# Arriquitaun.net
KiCad netlist of a schematic drawn in Altium Designer
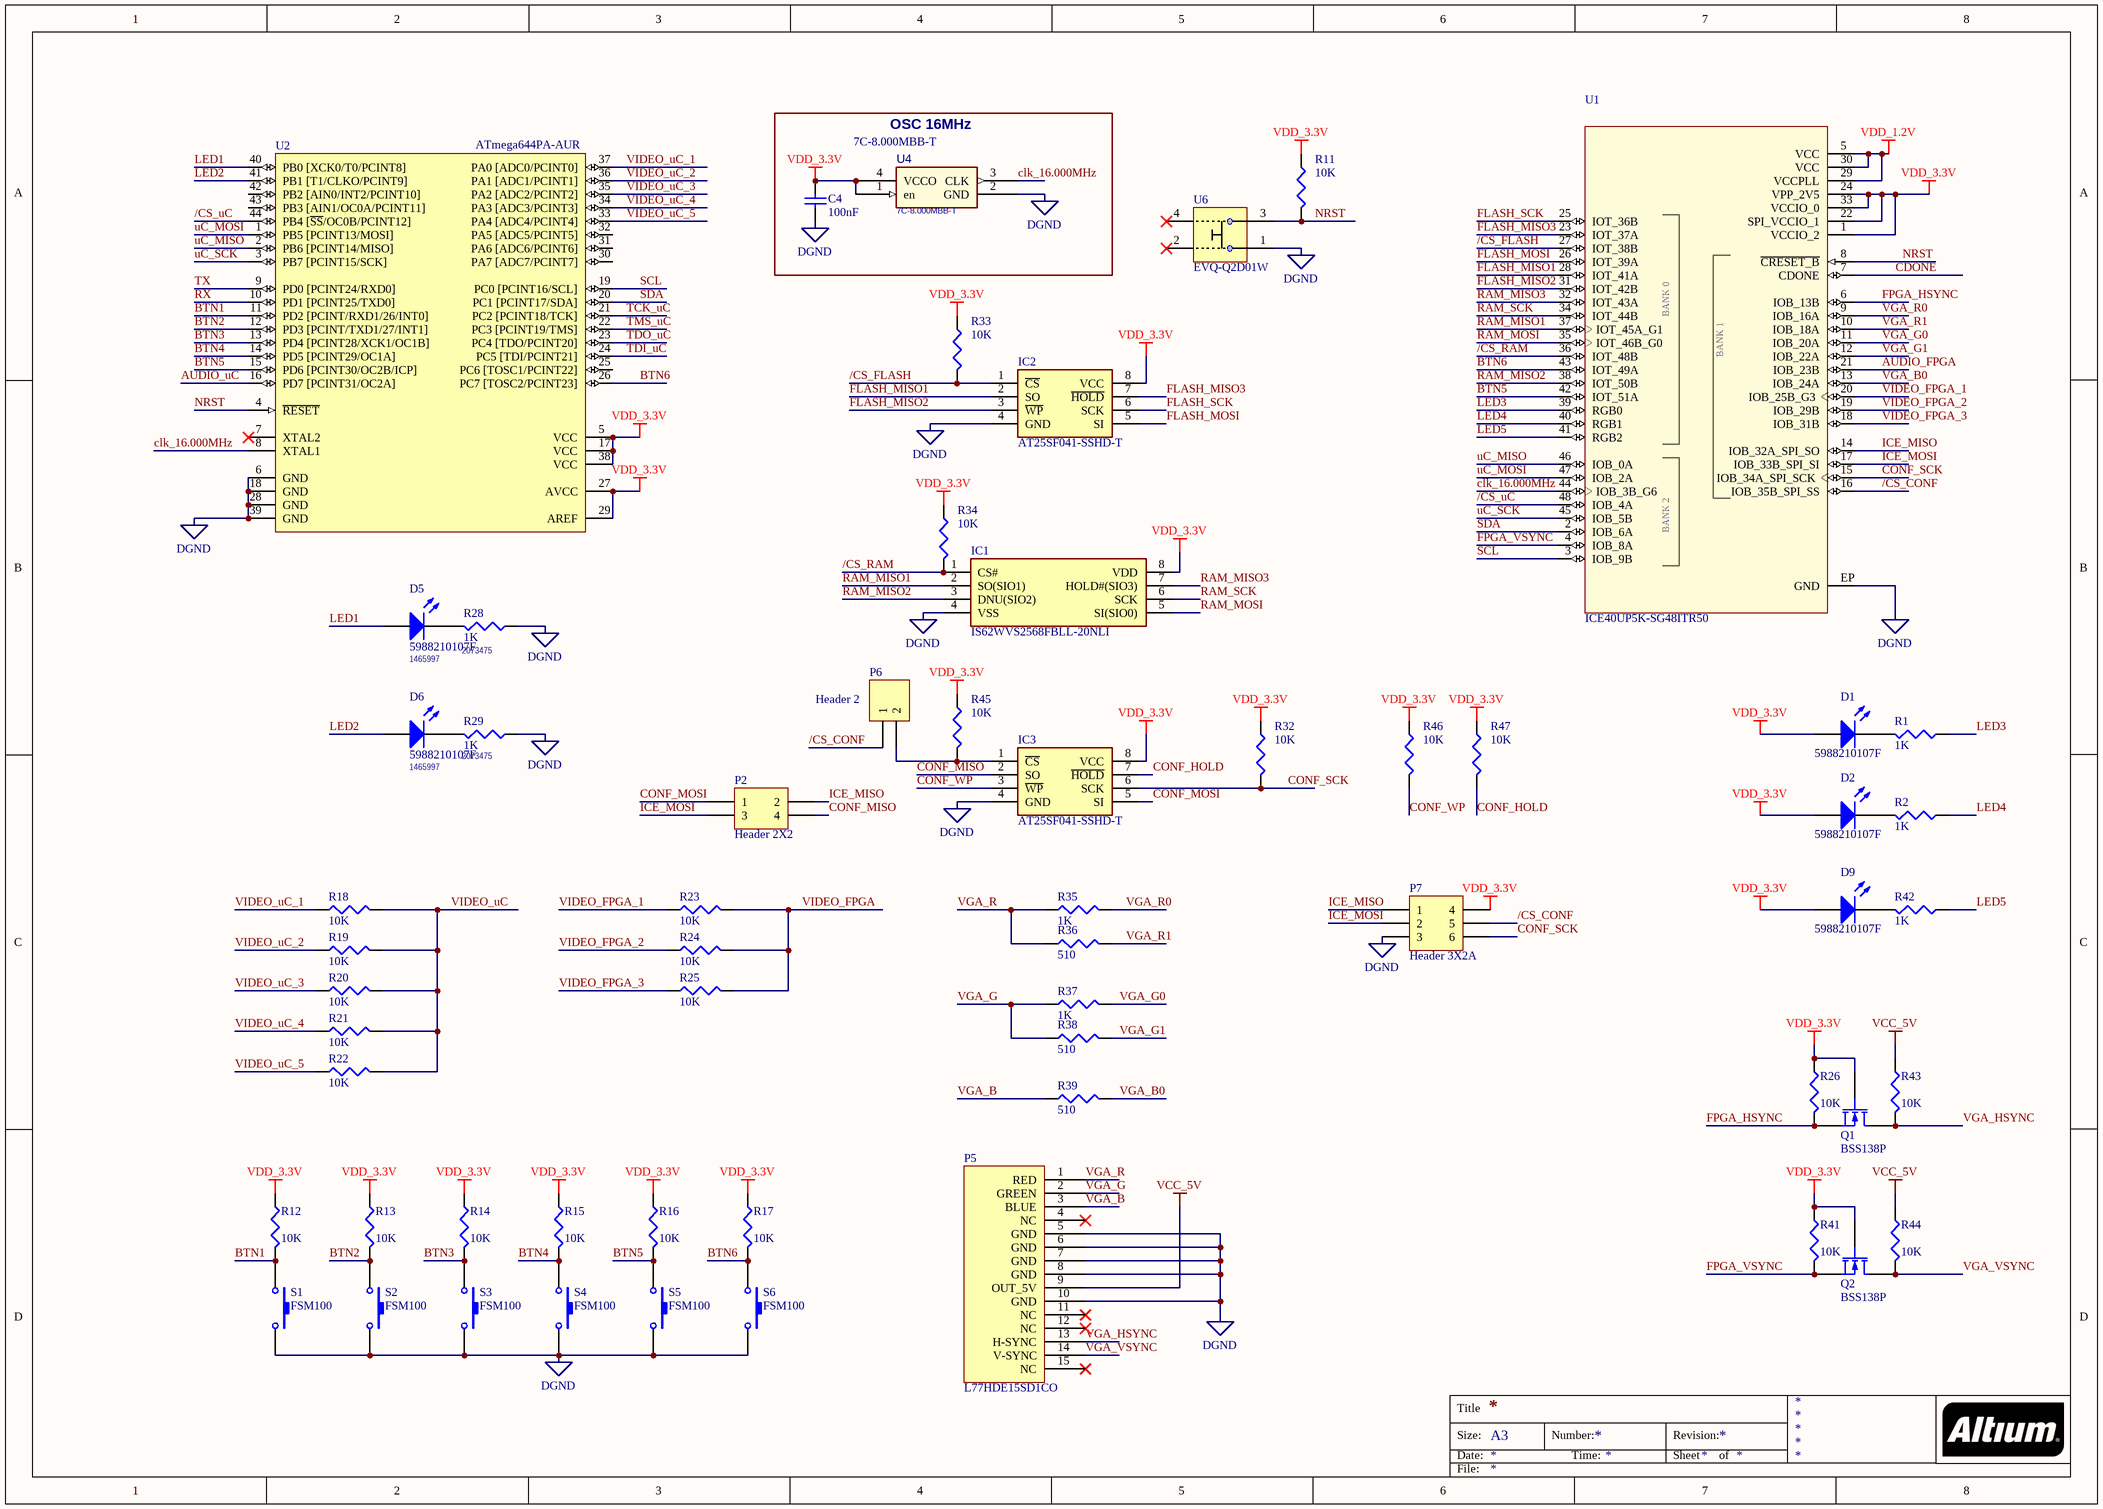
[diagram p0: Arriquitaun.SchDoc]

(export (version "E")
  (design (tool "Eeschema 10.0.6"))
  (components
    (comp (ref "C4")
      (value "100nF")
      (footprint "C1206")
      (description "Capacitor (Semiconductor SIM Model)")
      (fields (field (name "Comment") "Cap Semi") (field (name "PUBLISHER") "Altium Limited"))
      (libsource (lib "Miscellaneous Devices") (part "Cap Semi"))
    )
    (comp (ref "D1")
      (value "5988210107F")
      (footprint "1206 - LED")
      (description "LED, Rojo, Montaje Superficial, 1206 (Métrico 3216), 20 mA, 2 V, 640 nm")
      (fields (field (name "PUBLISHER") "Altium Limited"))
      (libsource (lib "Arriquitaun") (part "5988210107F"))
    )
    (comp (ref "D2")
      (value "5988210107F")
      (footprint "1206 - LED")
      (description "LED, Rojo, Montaje Superficial, 1206 (Métrico 3216), 20 mA, 2 V, 640 nm")
      (fields (field (name "PUBLISHER") "Altium Limited"))
      (libsource (lib "Arriquitaun") (part "5988210107F"))
    )
    (comp (ref "D5")
      (value "5988210107F")
      (footprint "1206 - LED")
      (description "LED, Rojo, Montaje Superficial, 1206 (Métrico 3216), 20 mA, 2 V, 640 nm")
      (fields (field (name "SUPPLIER PART NUMBER 1") "1465997") (field (name "PUBLISHER") "Altium Limited"))
      (libsource (lib "Arriquitaun") (part "5988210107F"))
    )
    (comp (ref "D6")
      (value "5988210107F")
      (footprint "1206 - LED")
      (description "LED, Rojo, Montaje Superficial, 1206 (Métrico 3216), 20 mA, 2 V, 640 nm")
      (fields (field (name "SUPPLIER PART NUMBER 1") "1465997") (field (name "PUBLISHER") "Altium Limited"))
      (libsource (lib "Arriquitaun") (part "5988210107F"))
    )
    (comp (ref "D9")
      (value "5988210107F")
      (footprint "1206 - LED")
      (description "LED, Rojo, Montaje Superficial, 1206 (Métrico 3216), 20 mA, 2 V, 640 nm")
      (fields (field (name "PUBLISHER") "Altium Limited"))
      (libsource (lib "Arriquitaun") (part "5988210107F"))
    )
    (comp (ref "IC1")
      (value "IS62WVS2568FBLL-20NLI")
      (footprint "SOIC127P600X175-8N")
      (description "SRAM 2Mb 256Kx8 20MHz 2.2-3.6V Serial SRAM")
      (fields (field (name "MOUSER PART NUMBER") "870-WVS2568FBLL20NLI"))
      (libsource (lib "Arriquitaun") (part "IS62WVS2568FBLL-20NLI"))
    )
    (comp (ref "IC2")
      (value "AT25SF041-SSHD-T")
      (footprint "SOIC127P600X175-8N")
      (description "Flash NOR 4Mb, 2.5-3.6V,104Mhz Serial Flash")
      (fields (field (name "MOUSER PART NUMBER") "988-AT25SF041-SSHD-T"))
      (libsource (lib "Arriquitaun") (part "AT25SF041-SSHD-T"))
    )
    (comp (ref "IC3")
      (value "AT25SF041-SSHD-T")
      (footprint "SOIC127P600X175-8N")
      (description "Flash NOR 4Mb, 2.5-3.6V,104Mhz Serial Flash")
      (fields (field (name "MOUSER PART NUMBER") "988-AT25SF041-SSHD-T"))
      (libsource (lib "Arriquitaun") (part "AT25SF041-SSHD-T"))
    )
    (comp (ref "P2")
      (value "Header 2X2")
      (footprint "HDR2X2")
      (description "Header, 2-Pin, Dual row")
      (fields (field (name "PUBLISHER") "Altium Limited"))
      (libsource (lib "Miscellaneous Connectors") (part "Header 2X2"))
    )
    (comp (ref "P5")
      (value "L77HDE15SD1CO")
      (footprint "DVI-15")
      (description "D-Sub High Density Connectors D SUB")
      (libsource (lib "Arriquitaun") (part "L77HDE15SD1CO"))
    )
    (comp (ref "P6")
      (value "Header 2")
      (footprint "HDR1X2")
      (description "Header, 2-Pin")
      (fields (field (name "PUBLISHER") "Altium Limited"))
      (libsource (lib "Miscellaneous Connectors") (part "Header 2"))
    )
    (comp (ref "P7")
      (value "Header 3X2A")
      (footprint "HDR2X3_CEN")
      (description "Header, 3-Pin, Dual row")
      (fields (field (name "PUBLISHER") "Altium Limited"))
      (libsource (lib "Miscellaneous Connectors") (part "Header 3X2A"))
    )
    (comp (ref "Q1")
      (value "BSS138P")
      (footprint "*SOT23-W")
      (description "MOSFET N-CH 60 V 360 mA")
      (libsource (lib "Arriquitaun") (part "BSS138P"))
    )
    (comp (ref "Q2")
      (value "BSS138P")
      (footprint "*SOT23-W")
      (description "MOSFET N-CH 60 V 360 mA")
      (libsource (lib "Arriquitaun") (part "BSS138P"))
    )
    (comp (ref "R1")
      (value "1K")
      (footprint "c1206")
      (description "Resistor")
      (fields (field (name "Comment") "Res3") (field (name "PUBLISHER") "Altium Limited"))
      (libsource (lib "Miscellaneous Devices") (part "Res3"))
    )
    (comp (ref "R2")
      (value "1K")
      (footprint "c1206")
      (description "Resistor")
      (fields (field (name "Comment") "Res3") (field (name "PUBLISHER") "Altium Limited"))
      (libsource (lib "Miscellaneous Devices") (part "Res3"))
    )
    (comp (ref "R11")
      (value "10K")
      (footprint "c1206")
      (description "Resistor")
      (fields (field (name "Comment") "Res3") (field (name "PUBLISHER") "Altium Limited"))
      (libsource (lib "Miscellaneous Devices") (part "Res3"))
    )
    (comp (ref "R12")
      (value "10K")
      (footprint "c1206")
      (description "Resistor")
      (fields (field (name "Comment") "Res3") (field (name "PUBLISHER") "Altium Limited"))
      (libsource (lib "Miscellaneous Devices") (part "Res3"))
    )
    (comp (ref "R13")
      (value "10K")
      (footprint "c1206")
      (description "Resistor")
      (fields (field (name "Comment") "Res3") (field (name "PUBLISHER") "Altium Limited"))
      (libsource (lib "Miscellaneous Devices") (part "Res3"))
    )
    (comp (ref "R14")
      (value "10K")
      (footprint "c1206")
      (description "Resistor")
      (fields (field (name "Comment") "Res3") (field (name "PUBLISHER") "Altium Limited"))
      (libsource (lib "Miscellaneous Devices") (part "Res3"))
    )
    (comp (ref "R15")
      (value "10K")
      (footprint "c1206")
      (description "Resistor")
      (fields (field (name "Comment") "Res3") (field (name "PUBLISHER") "Altium Limited"))
      (libsource (lib "Miscellaneous Devices") (part "Res3"))
    )
    (comp (ref "R16")
      (value "10K")
      (footprint "c1206")
      (description "Resistor")
      (fields (field (name "Comment") "Res3") (field (name "PUBLISHER") "Altium Limited"))
      (libsource (lib "Miscellaneous Devices") (part "Res3"))
    )
    (comp (ref "R17")
      (value "10K")
      (footprint "c1206")
      (description "Resistor")
      (fields (field (name "Comment") "Res3") (field (name "PUBLISHER") "Altium Limited"))
      (libsource (lib "Miscellaneous Devices") (part "Res3"))
    )
    (comp (ref "R18")
      (value "10K")
      (footprint "c1206")
      (description "Resistor")
      (fields (field (name "Comment") "Res3") (field (name "PUBLISHER") "Altium Limited"))
      (libsource (lib "Miscellaneous Devices") (part "Res3"))
    )
    (comp (ref "R19")
      (value "10K")
      (footprint "c1206")
      (description "Resistor")
      (fields (field (name "Comment") "Res3") (field (name "PUBLISHER") "Altium Limited"))
      (libsource (lib "Miscellaneous Devices") (part "Res3"))
    )
    (comp (ref "R20")
      (value "10K")
      (footprint "c1206")
      (description "Resistor")
      (fields (field (name "Comment") "Res3") (field (name "PUBLISHER") "Altium Limited"))
      (libsource (lib "Miscellaneous Devices") (part "Res3"))
    )
    (comp (ref "R21")
      (value "10K")
      (footprint "c1206")
      (description "Resistor")
      (fields (field (name "Comment") "Res3") (field (name "PUBLISHER") "Altium Limited"))
      (libsource (lib "Miscellaneous Devices") (part "Res3"))
    )
    (comp (ref "R22")
      (value "10K")
      (footprint "c1206")
      (description "Resistor")
      (fields (field (name "Comment") "Res3") (field (name "PUBLISHER") "Altium Limited"))
      (libsource (lib "Miscellaneous Devices") (part "Res3"))
    )
    (comp (ref "R23")
      (value "10K")
      (footprint "c1206")
      (description "Resistor")
      (fields (field (name "Comment") "Res3") (field (name "PUBLISHER") "Altium Limited"))
      (libsource (lib "Miscellaneous Devices") (part "Res3"))
    )
    (comp (ref "R24")
      (value "10K")
      (footprint "c1206")
      (description "Resistor")
      (fields (field (name "Comment") "Res3") (field (name "PUBLISHER") "Altium Limited"))
      (libsource (lib "Miscellaneous Devices") (part "Res3"))
    )
    (comp (ref "R25")
      (value "10K")
      (footprint "c1206")
      (description "Resistor")
      (fields (field (name "Comment") "Res3") (field (name "PUBLISHER") "Altium Limited"))
      (libsource (lib "Miscellaneous Devices") (part "Res3"))
    )
    (comp (ref "R26")
      (value "10K")
      (footprint "c1206")
      (description "Resistor")
      (fields (field (name "Comment") "Res3") (field (name "PUBLISHER") "Altium Limited"))
      (libsource (lib "Miscellaneous Devices") (part "Res3"))
    )
    (comp (ref "R28")
      (value "1K")
      (footprint "c1206")
      (description "Resistor")
      (fields
        (field (name "SUPPLIER PART NUMBER 1") "2073475")
        (field (name "Comment") "Res3")
        (field (name "PUBLISHER") "Altium Limited")
      )
      (libsource (lib "Miscellaneous Devices") (part "Res3"))
    )
    (comp (ref "R29")
      (value "1K")
      (footprint "c1206")
      (description "Resistor")
      (fields
        (field (name "SUPPLIER PART NUMBER 1") "2073475")
        (field (name "Comment") "Res3")
        (field (name "PUBLISHER") "Altium Limited")
      )
      (libsource (lib "Miscellaneous Devices") (part "Res3"))
    )
    (comp (ref "R32")
      (value "10K")
      (footprint "c1206")
      (description "Resistor")
      (fields (field (name "Comment") "Res3") (field (name "PUBLISHER") "Altium Limited"))
      (libsource (lib "Miscellaneous Devices") (part "Res3"))
    )
    (comp (ref "R33")
      (value "10K")
      (footprint "c1206")
      (description "Resistor")
      (fields (field (name "Comment") "Res3") (field (name "PUBLISHER") "Altium Limited"))
      (libsource (lib "Miscellaneous Devices") (part "Res3"))
    )
    (comp (ref "R34")
      (value "10K")
      (footprint "c1206")
      (description "Resistor")
      (fields (field (name "Comment") "Res3") (field (name "PUBLISHER") "Altium Limited"))
      (libsource (lib "Miscellaneous Devices") (part "Res3"))
    )
    (comp (ref "R35")
      (value "1K")
      (footprint "c1206")
      (description "Resistor")
      (fields (field (name "Comment") "Res3") (field (name "PUBLISHER") "Altium Limited"))
      (libsource (lib "Miscellaneous Devices") (part "Res3"))
    )
    (comp (ref "R36")
      (value "510")
      (footprint "c1206")
      (description "Resistor")
      (fields (field (name "Comment") "Res3") (field (name "PUBLISHER") "Altium Limited"))
      (libsource (lib "Miscellaneous Devices") (part "Res3"))
    )
    (comp (ref "R37")
      (value "1K")
      (footprint "c1206")
      (description "Resistor")
      (fields (field (name "Comment") "Res3") (field (name "PUBLISHER") "Altium Limited"))
      (libsource (lib "Miscellaneous Devices") (part "Res3"))
    )
    (comp (ref "R38")
      (value "510")
      (footprint "c1206")
      (description "Resistor")
      (fields (field (name "Comment") "Res3") (field (name "PUBLISHER") "Altium Limited"))
      (libsource (lib "Miscellaneous Devices") (part "Res3"))
    )
    (comp (ref "R39")
      (value "510")
      (footprint "c1206")
      (description "Resistor")
      (fields (field (name "Comment") "Res3") (field (name "PUBLISHER") "Altium Limited"))
      (libsource (lib "Miscellaneous Devices") (part "Res3"))
    )
    (comp (ref "R41")
      (value "10K")
      (footprint "c1206")
      (description "Resistor")
      (fields (field (name "Comment") "Res3") (field (name "PUBLISHER") "Altium Limited"))
      (libsource (lib "Miscellaneous Devices") (part "Res3"))
    )
    (comp (ref "R42")
      (value "1K")
      (footprint "c1206")
      (description "Resistor")
      (fields (field (name "Comment") "Res3") (field (name "PUBLISHER") "Altium Limited"))
      (libsource (lib "Miscellaneous Devices") (part "Res3"))
    )
    (comp (ref "R43")
      (value "10K")
      (footprint "c1206")
      (description "Resistor")
      (fields (field (name "Comment") "Res3") (field (name "PUBLISHER") "Altium Limited"))
      (libsource (lib "Miscellaneous Devices") (part "Res3"))
    )
    (comp (ref "R44")
      (value "10K")
      (footprint "c1206")
      (description "Resistor")
      (fields (field (name "Comment") "Res3") (field (name "PUBLISHER") "Altium Limited"))
      (libsource (lib "Miscellaneous Devices") (part "Res3"))
    )
    (comp (ref "R45")
      (value "10K")
      (footprint "c1206")
      (description "Resistor")
      (fields (field (name "Comment") "Res3") (field (name "PUBLISHER") "Altium Limited"))
      (libsource (lib "Miscellaneous Devices") (part "Res3"))
    )
    (comp (ref "R46")
      (value "10K")
      (footprint "c1206")
      (description "Resistor")
      (fields (field (name "Comment") "Res3") (field (name "PUBLISHER") "Altium Limited"))
      (libsource (lib "Miscellaneous Devices") (part "Res3"))
    )
    (comp (ref "R47")
      (value "10K")
      (footprint "c1206")
      (description "Resistor")
      (fields (field (name "Comment") "Res3") (field (name "PUBLISHER") "Altium Limited"))
      (libsource (lib "Miscellaneous Devices") (part "Res3"))
    )
    (comp (ref "S1")
      (value "FSM100")
      (footprint "FSM100")
      (description "Interruptores táctiles 12mm FLSH OFF-(ON)")
      (fields (field (name "PUBLISHER") "Altium Limited"))
      (libsource (lib "Arriquitaun") (part "FSM100"))
    )
    (comp (ref "S2")
      (value "FSM100")
      (footprint "FSM100")
      (description "Interruptores táctiles 12mm FLSH OFF-(ON)")
      (fields (field (name "PUBLISHER") "Altium Limited"))
      (libsource (lib "Arriquitaun") (part "FSM100"))
    )
    (comp (ref "S3")
      (value "FSM100")
      (footprint "FSM100")
      (description "Interruptores táctiles 12mm FLSH OFF-(ON)")
      (fields (field (name "PUBLISHER") "Altium Limited"))
      (libsource (lib "Arriquitaun") (part "FSM100"))
    )
    (comp (ref "S4")
      (value "FSM100")
      (footprint "FSM100")
      (description "Interruptores táctiles 12mm FLSH OFF-(ON)")
      (fields (field (name "PUBLISHER") "Altium Limited"))
      (libsource (lib "Arriquitaun") (part "FSM100"))
    )
    (comp (ref "S5")
      (value "FSM100")
      (footprint "FSM100")
      (description "Interruptores táctiles 12mm FLSH OFF-(ON)")
      (fields (field (name "PUBLISHER") "Altium Limited"))
      (libsource (lib "Arriquitaun") (part "FSM100"))
    )
    (comp (ref "S6")
      (value "FSM100")
      (footprint "FSM100")
      (description "Interruptores táctiles 12mm FLSH OFF-(ON)")
      (fields (field (name "PUBLISHER") "Altium Limited"))
      (libsource (lib "Arriquitaun") (part "FSM100"))
    )
    (comp (ref "U1")
      (value "ICE40UP5K-SG48ITR50")
      (footprint "*QFN50P700X700X100-49N_ICE40UP5K-SG48ITR50(Primary)")
      (description "iCE40 UltraPlus 5280 LUTs 39 I/O 1.2 V Surface Mount FOPGA - QFN-48")
      (fields (field (name "MF") "Lattice Semiconductor"))
      (libsource (lib "Arriquitaun") (part "ICE40UP5K-SG48ITR50"))
    )
    (comp (ref "U2")
      (value "ATmega644PA-AUR")
      (footprint "44A_N")
      (fields (field (name "PUBLISHER") "Altium Limited"))
      (libsource (lib "Arriquitaun") (part "ATmega644PA-AUR"))
    )
    (comp (ref "U4")
      (value "7C-8.000MBB-T")
      (description "Osciladores de reloj estándar 8 8.000MHz 3.3V50ppm(-10 +70C)")
      (fields (field (name "SUPPLIER PART NUMBER 3") "7C-8.000MBB-T"))
      (libsource (lib "Arriquitaun") (part "7C-8.000MBB-T"))
    )
    (comp (ref "U6")
      (value "EVQ-Q2D01W")
      (footprint "PUSHBUTTON")
      (description "Interruptores táctiles Switch Light Touch 6mm Square SMD")
      (libsource (lib "Arriquitaun") (part "EVQ-Q2D01W"))
    )
  )
  (nets
    (net (code "1") (name "/AUDIO_FPGA") (class "Default")
      (node (ref "U1") (pin "21") (pinfunction "IOB_23B_21") (pintype "bidirectional"))
    )
    (net (code "2") (name "/AUDIO_uC") (class "Default")
      (node (ref "U2") (pin "16") (pinfunction "PD7_[PCINT31/OC2A]_16") (pintype "bidirectional"))
    )
    (net (code "3") (name "/BTN1") (class "Default")
      (node (ref "R12") (pin "2") (pinfunction "2_2") (pintype "passive"))
      (node (ref "S1") (pin "1") (pinfunction "1_1") (pintype "passive"))
      (node (ref "U2") (pin "11") (pinfunction "PD2_[PCINT/RXD1/26/INT0]_11") (pintype "bidirectional"))
    )
    (net (code "4") (name "/BTN2") (class "Default")
      (node (ref "R13") (pin "2") (pinfunction "2_2") (pintype "passive"))
      (node (ref "S2") (pin "1") (pinfunction "1_1") (pintype "passive"))
      (node (ref "U2") (pin "12") (pinfunction "PD3_[PCINT/TXD1/27/INT1]_12") (pintype "bidirectional"))
    )
    (net (code "5") (name "/BTN3") (class "Default")
      (node (ref "R14") (pin "2") (pinfunction "2_2") (pintype "passive"))
      (node (ref "S3") (pin "1") (pinfunction "1_1") (pintype "passive"))
      (node (ref "U2") (pin "13") (pinfunction "PD4_[PCINT28/XCK1/OC1B]_13") (pintype "bidirectional"))
    )
    (net (code "6") (name "/BTN4") (class "Default")
      (node (ref "R15") (pin "2") (pinfunction "2_2") (pintype "passive"))
      (node (ref "S4") (pin "1") (pinfunction "1_1") (pintype "passive"))
      (node (ref "U2") (pin "14") (pinfunction "PD5_[PCINT29/OC1A]_14") (pintype "bidirectional"))
    )
    (net (code "7") (name "/BTN5") (class "Default")
      (node (ref "R16") (pin "2") (pinfunction "2_2") (pintype "passive"))
      (node (ref "S5") (pin "1") (pinfunction "1_1") (pintype "passive"))
      (node (ref "U1") (pin "42") (pinfunction "IOT_51A_42") (pintype "bidirectional"))
      (node (ref "U2") (pin "15") (pinfunction "PD6_[PCINT30/OC2B/ICP]_15") (pintype "bidirectional"))
    )
    (net (code "8") (name "/BTN6") (class "Default")
      (node (ref "R17") (pin "2") (pinfunction "2_2") (pintype "passive"))
      (node (ref "S6") (pin "1") (pinfunction "1_1") (pintype "passive"))
      (node (ref "U1") (pin "43") (pinfunction "IOT_49A_43") (pintype "bidirectional"))
      (node (ref "U2") (pin "26") (pinfunction "PC7_[TOSC2/PCINT23]_26") (pintype "bidirectional"))
    )
    (net (code "9") (name "/CDONE") (class "Default")
      (node (ref "U1") (pin "7") (pinfunction "CDONE_7") (pintype "bidirectional"))
    )
    (net (code "10") (name "/CONF_HOLD") (class "Default")
      (node (ref "IC3") (pin "7") (pinfunction "~{HOLD}_7") (pintype "passive"))
      (node (ref "R47") (pin "2") (pinfunction "2_2") (pintype "passive"))
    )
    (net (code "11") (name "/CONF_MISO") (class "Default")
      (node (ref "IC3") (pin "2") (pinfunction "SO_2") (pintype "passive"))
      (node (ref "P2") (pin "4") (pinfunction "4_4") (pintype "passive"))
    )
    (net (code "12") (name "/CONF_MOSI") (class "Default")
      (node (ref "IC3") (pin "5") (pinfunction "SI_5") (pintype "passive"))
      (node (ref "P2") (pin "1") (pinfunction "1_1") (pintype "passive"))
    )
    (net (code "13") (name "/CONF_SCK") (class "Default")
      (node (ref "IC3") (pin "6") (pinfunction "SCK_6") (pintype "passive"))
      (node (ref "P7") (pin "6") (pinfunction "6_6") (pintype "passive"))
      (node (ref "R32") (pin "2") (pinfunction "2_2") (pintype "passive"))
      (node (ref "U1") (pin "15") (pinfunction "IOB_34A_SPI_SCK_15") (pintype "bidirectional"))
    )
    (net (code "14") (name "/CONF_WP") (class "Default")
      (node (ref "IC3") (pin "3") (pinfunction "~{WP}_3") (pintype "passive"))
      (node (ref "R46") (pin "2") (pinfunction "2_2") (pintype "passive"))
    )
    (net (code "15") (name "/FLASH_MISO1") (class "Default")
      (node (ref "IC2") (pin "2") (pinfunction "SO_2") (pintype "passive"))
      (node (ref "U1") (pin "28") (pinfunction "IOT_41A_28") (pintype "bidirectional"))
    )
    (net (code "16") (name "/FLASH_MISO2") (class "Default")
      (node (ref "IC2") (pin "3") (pinfunction "~{WP}_3") (pintype "passive"))
      (node (ref "U1") (pin "31") (pinfunction "IOT_42B_31") (pintype "bidirectional"))
    )
    (net (code "17") (name "/FLASH_MISO3") (class "Default")
      (node (ref "IC2") (pin "7") (pinfunction "~{HOLD}_7") (pintype "passive"))
      (node (ref "U1") (pin "23") (pinfunction "IOT_37A_23") (pintype "bidirectional"))
    )
    (net (code "18") (name "/FLASH_MOSI") (class "Default")
      (node (ref "IC2") (pin "5") (pinfunction "SI_5") (pintype "passive"))
      (node (ref "U1") (pin "26") (pinfunction "IOT_39A_26") (pintype "bidirectional"))
    )
    (net (code "19") (name "/FLASH_SCK") (class "Default")
      (node (ref "IC2") (pin "6") (pinfunction "SCK_6") (pintype "passive"))
      (node (ref "U1") (pin "25") (pinfunction "IOT_36B_25") (pintype "bidirectional"))
    )
    (net (code "20") (name "/FPGA_HSYNC") (class "Default")
      (node (ref "Q1") (pin "2") (pinfunction "S_2") (pintype "passive"))
      (node (ref "R26") (pin "2") (pinfunction "2_2") (pintype "passive"))
      (node (ref "U1") (pin "6") (pinfunction "IOB_13B_6") (pintype "bidirectional"))
    )
    (net (code "21") (name "/FPGA_VSYNC") (class "Default")
      (node (ref "Q2") (pin "2") (pinfunction "S_2") (pintype "passive"))
      (node (ref "R41") (pin "2") (pinfunction "2_2") (pintype "passive"))
      (node (ref "U1") (pin "4") (pinfunction "IOB_8A_4") (pintype "bidirectional"))
    )
    (net (code "22") (name "/ICE_MISO") (class "Default")
      (node (ref "P2") (pin "2") (pinfunction "2_2") (pintype "passive"))
      (node (ref "P7") (pin "1") (pinfunction "1_1") (pintype "passive"))
      (node (ref "U1") (pin "14") (pinfunction "IOB_32A_SPI_SO_14") (pintype "bidirectional"))
    )
    (net (code "23") (name "/ICE_MOSI") (class "Default")
      (node (ref "P2") (pin "3") (pinfunction "3_3") (pintype "passive"))
      (node (ref "P7") (pin "2") (pinfunction "2_2") (pintype "passive"))
      (node (ref "U1") (pin "17") (pinfunction "IOB_33B_SPI_SI_17") (pintype "bidirectional"))
    )
    (net (code "24") (name "/LED1") (class "Default")
      (node (ref "D5") (pin "1") (pinfunction "A_1") (pintype "passive"))
      (node (ref "U2") (pin "40") (pinfunction "PB0_[XCK0/T0/PCINT8]_40") (pintype "bidirectional"))
    )
    (net (code "25") (name "/LED2") (class "Default")
      (node (ref "D6") (pin "1") (pinfunction "A_1") (pintype "passive"))
      (node (ref "U2") (pin "41") (pinfunction "PB1_[T1/CLKO/PCINT9]_41") (pintype "bidirectional"))
    )
    (net (code "26") (name "/LED3") (class "Default")
      (node (ref "R1") (pin "1") (pinfunction "1_1") (pintype "passive"))
      (node (ref "U1") (pin "39") (pinfunction "RGB0_39") (pintype "bidirectional"))
    )
    (net (code "27") (name "/LED4") (class "Default")
      (node (ref "R2") (pin "1") (pinfunction "1_1") (pintype "passive"))
      (node (ref "U1") (pin "40") (pinfunction "RGB1_40") (pintype "bidirectional"))
    )
    (net (code "28") (name "/LED5") (class "Default")
      (node (ref "R42") (pin "1") (pinfunction "1_1") (pintype "passive"))
      (node (ref "U1") (pin "41") (pinfunction "RGB2_41") (pintype "bidirectional"))
    )
    (net (code "29") (name "/NRST") (class "Default")
      (node (ref "R11") (pin "2") (pinfunction "2_2") (pintype "passive"))
      (node (ref "U1") (pin "8") (pinfunction "~{CRESET_B}_8") (pintype "input"))
      (node (ref "U2") (pin "4") (pinfunction "~{RESET}_4") (pintype "input"))
      (node (ref "U6") (pin "3") (pinfunction "3_3") (pintype "passive"))
    )
    (net (code "30") (name "/RAM_MISO1") (class "Default")
      (node (ref "IC1") (pin "2") (pinfunction "SO(SIO1)_2") (pintype "passive"))
      (node (ref "U1") (pin "37") (pinfunction "IOT_45A_G1_37") (pintype "bidirectional"))
    )
    (net (code "31") (name "/RAM_MISO2") (class "Default")
      (node (ref "IC1") (pin "3") (pinfunction "DNU(SIO2)_3") (pintype "passive"))
      (node (ref "U1") (pin "38") (pinfunction "IOT_50B_38") (pintype "bidirectional"))
    )
    (net (code "32") (name "/RAM_MISO3") (class "Default")
      (node (ref "IC1") (pin "7") (pinfunction "HOLD#(SIO3)_7") (pintype "passive"))
      (node (ref "U1") (pin "32") (pinfunction "IOT_43A_32") (pintype "bidirectional"))
    )
    (net (code "33") (name "/RAM_MOSI") (class "Default")
      (node (ref "IC1") (pin "5") (pinfunction "SI(SIO0)_5") (pintype "passive"))
      (node (ref "U1") (pin "35") (pinfunction "IOT_46B_G0_35") (pintype "bidirectional"))
    )
    (net (code "34") (name "/RAM_SCK") (class "Default")
      (node (ref "IC1") (pin "6") (pinfunction "SCK_6") (pintype "passive"))
      (node (ref "U1") (pin "34") (pinfunction "IOT_44B_34") (pintype "bidirectional"))
    )
    (net (code "35") (name "/RX") (class "Default")
      (node (ref "U2") (pin "10") (pinfunction "PD1_[PCINT25/TXD0]_10") (pintype "bidirectional"))
    )
    (net (code "36") (name "/SCL") (class "Default")
      (node (ref "U1") (pin "3") (pinfunction "IOB_9B_3") (pintype "bidirectional"))
      (node (ref "U2") (pin "19") (pinfunction "PC0_[PCINT16/SCL]_19") (pintype "bidirectional"))
    )
    (net (code "37") (name "/SDA") (class "Default")
      (node (ref "U1") (pin "2") (pinfunction "IOB_6A_2") (pintype "bidirectional"))
      (node (ref "U2") (pin "20") (pinfunction "PC1_[PCINT17/SDA]_20") (pintype "bidirectional"))
    )
    (net (code "38") (name "/TCK_uC") (class "Default")
      (node (ref "U2") (pin "21") (pinfunction "PC2_[PCINT18/TCK]_21") (pintype "bidirectional"))
    )
    (net (code "39") (name "/TDI_uC") (class "Default")
      (node (ref "U2") (pin "24") (pinfunction "PC5_[TDI/PCINT21]_24") (pintype "bidirectional"))
    )
    (net (code "40") (name "/TDO_uC") (class "Default")
      (node (ref "U2") (pin "23") (pinfunction "PC4_[TDO/PCINT20]_23") (pintype "bidirectional"))
    )
    (net (code "41") (name "/TMS_uC") (class "Default")
      (node (ref "U2") (pin "22") (pinfunction "PC3_[PCINT19/TMS]_22") (pintype "bidirectional"))
    )
    (net (code "42") (name "/TX") (class "Default")
      (node (ref "U2") (pin "9") (pinfunction "PD0_[PCINT24/RXD0]_9") (pintype "bidirectional"))
    )
    (net (code "43") (name "/VGA_B") (class "Default")
      (node (ref "P5") (pin "3") (pinfunction "BLUE_3") (pintype "passive"))
      (node (ref "R39") (pin "1") (pinfunction "1_1") (pintype "passive"))
    )
    (net (code "44") (name "/VGA_B0") (class "Default")
      (node (ref "R39") (pin "2") (pinfunction "2_2") (pintype "passive"))
      (node (ref "U1") (pin "13") (pinfunction "IOB_24A_13") (pintype "bidirectional"))
    )
    (net (code "45") (name "/VGA_G") (class "Default")
      (node (ref "P5") (pin "2") (pinfunction "GREEN_2") (pintype "passive"))
      (node (ref "R37") (pin "1") (pinfunction "1_1") (pintype "passive"))
      (node (ref "R38") (pin "1") (pinfunction "1_1") (pintype "passive"))
    )
    (net (code "46") (name "/VGA_G0") (class "Default")
      (node (ref "R37") (pin "2") (pinfunction "2_2") (pintype "passive"))
      (node (ref "U1") (pin "11") (pinfunction "IOB_20A_11") (pintype "bidirectional"))
    )
    (net (code "47") (name "/VGA_G1") (class "Default")
      (node (ref "R38") (pin "2") (pinfunction "2_2") (pintype "passive"))
      (node (ref "U1") (pin "12") (pinfunction "IOB_22A_12") (pintype "bidirectional"))
    )
    (net (code "48") (name "/VGA_HSYNC") (class "Default")
      (node (ref "P5") (pin "13") (pinfunction "H-SYNC_13") (pintype "passive"))
      (node (ref "Q1") (pin "3") (pinfunction "D_3") (pintype "passive"))
      (node (ref "R43") (pin "2") (pinfunction "2_2") (pintype "passive"))
    )
    (net (code "49") (name "/VGA_R") (class "Default")
      (node (ref "P5") (pin "1") (pinfunction "RED_1") (pintype "passive"))
      (node (ref "R35") (pin "1") (pinfunction "1_1") (pintype "passive"))
      (node (ref "R36") (pin "1") (pinfunction "1_1") (pintype "passive"))
    )
    (net (code "50") (name "/VGA_R0") (class "Default")
      (node (ref "R35") (pin "2") (pinfunction "2_2") (pintype "passive"))
      (node (ref "U1") (pin "9") (pinfunction "IOB_16A_9") (pintype "bidirectional"))
    )
    (net (code "51") (name "/VGA_R1") (class "Default")
      (node (ref "R36") (pin "2") (pinfunction "2_2") (pintype "passive"))
      (node (ref "U1") (pin "10") (pinfunction "IOB_18A_10") (pintype "bidirectional"))
    )
    (net (code "52") (name "/VGA_VSYNC") (class "Default")
      (node (ref "P5") (pin "14") (pinfunction "V-SYNC_14") (pintype "passive"))
      (node (ref "Q2") (pin "3") (pinfunction "D_3") (pintype "passive"))
      (node (ref "R44") (pin "2") (pinfunction "2_2") (pintype "passive"))
    )
    (net (code "53") (name "/VIDEO_FPGA") (class "Default")
      (node (ref "R23") (pin "2") (pinfunction "2_2") (pintype "passive"))
      (node (ref "R24") (pin "2") (pinfunction "2_2") (pintype "passive"))
      (node (ref "R25") (pin "2") (pinfunction "2_2") (pintype "passive"))
    )
    (net (code "54") (name "/VIDEO_FPGA_1") (class "Default")
      (node (ref "R23") (pin "1") (pinfunction "1_1") (pintype "passive"))
      (node (ref "U1") (pin "20") (pinfunction "IOB_25B_G3_20") (pintype "bidirectional"))
    )
    (net (code "55") (name "/VIDEO_FPGA_2") (class "Default")
      (node (ref "R24") (pin "1") (pinfunction "1_1") (pintype "passive"))
      (node (ref "U1") (pin "19") (pinfunction "IOB_29B_19") (pintype "bidirectional"))
    )
    (net (code "56") (name "/VIDEO_FPGA_3") (class "Default")
      (node (ref "R25") (pin "1") (pinfunction "1_1") (pintype "passive"))
      (node (ref "U1") (pin "18") (pinfunction "IOB_31B_18") (pintype "bidirectional"))
    )
    (net (code "57") (name "/VIDEO_uC") (class "Default")
      (node (ref "R18") (pin "2") (pinfunction "2_2") (pintype "passive"))
      (node (ref "R19") (pin "2") (pinfunction "2_2") (pintype "passive"))
      (node (ref "R20") (pin "2") (pinfunction "2_2") (pintype "passive"))
      (node (ref "R21") (pin "2") (pinfunction "2_2") (pintype "passive"))
      (node (ref "R22") (pin "2") (pinfunction "2_2") (pintype "passive"))
    )
    (net (code "58") (name "/VIDEO_uC_1") (class "Default")
      (node (ref "R18") (pin "1") (pinfunction "1_1") (pintype "passive"))
      (node (ref "U2") (pin "37") (pinfunction "PA0_[ADC0/PCINT0]_37") (pintype "bidirectional"))
    )
    (net (code "59") (name "/VIDEO_uC_2") (class "Default")
      (node (ref "R19") (pin "1") (pinfunction "1_1") (pintype "passive"))
      (node (ref "U2") (pin "36") (pinfunction "PA1_[ADC1/PCINT1]_36") (pintype "bidirectional"))
    )
    (net (code "60") (name "/VIDEO_uC_3") (class "Default")
      (node (ref "R20") (pin "1") (pinfunction "1_1") (pintype "passive"))
      (node (ref "U2") (pin "35") (pinfunction "PA2_[ADC2/PCINT2]_35") (pintype "bidirectional"))
    )
    (net (code "61") (name "/VIDEO_uC_4") (class "Default")
      (node (ref "R21") (pin "1") (pinfunction "1_1") (pintype "passive"))
      (node (ref "U2") (pin "34") (pinfunction "PA3_[ADC3/PCINT3]_34") (pintype "bidirectional"))
    )
    (net (code "62") (name "/VIDEO_uC_5") (class "Default")
      (node (ref "R22") (pin "1") (pinfunction "1_1") (pintype "passive"))
      (node (ref "U2") (pin "33") (pinfunction "PA4_[ADC4/PCINT4]_33") (pintype "bidirectional"))
    )
    (net (code "63") (name "/clk_16.000MHz") (class "Default")
      (node (ref "U1") (pin "44") (pinfunction "IOB_3B_G6_44") (pintype "bidirectional"))
      (node (ref "U2") (pin "8") (pinfunction "XTAL1_8") (pintype "passive"))
      (node (ref "U4") (pin "3") (pinfunction "CLK_3") (pintype "output"))
    )
    (net (code "64") (name "/uC_MISO") (class "Default")
      (node (ref "U1") (pin "46") (pinfunction "IOB_0A_46") (pintype "bidirectional"))
      (node (ref "U2") (pin "2") (pinfunction "PB6_[PCINT14/MISO]_2") (pintype "bidirectional"))
    )
    (net (code "65") (name "/uC_MOSI") (class "Default")
      (node (ref "U1") (pin "47") (pinfunction "IOB_2A_47") (pintype "bidirectional"))
      (node (ref "U2") (pin "1") (pinfunction "PB5_[PCINT13/MOSI]_1") (pintype "bidirectional"))
    )
    (net (code "66") (name "/uC_SCK") (class "Default")
      (node (ref "U1") (pin "45") (pinfunction "IOB_5B_45") (pintype "bidirectional"))
      (node (ref "U2") (pin "3") (pinfunction "PB7_[PCINT15/SCK]_3") (pintype "bidirectional"))
    )
    (net (code "67") (name "/{slash}CS_CONF") (class "Default")
      (node (ref "P6") (pin "1") (pinfunction "1_1") (pintype "passive"))
      (node (ref "P7") (pin "5") (pinfunction "5_5") (pintype "passive"))
      (node (ref "U1") (pin "16") (pinfunction "IOB_35B_SPI_SS_16") (pintype "bidirectional"))
    )
    (net (code "68") (name "/{slash}CS_FLASH") (class "Default")
      (node (ref "IC2") (pin "1") (pinfunction "~{CS}_1") (pintype "passive"))
      (node (ref "R33") (pin "2") (pinfunction "2_2") (pintype "passive"))
      (node (ref "U1") (pin "27") (pinfunction "IOT_38B_27") (pintype "bidirectional"))
    )
    (net (code "69") (name "/{slash}CS_RAM") (class "Default")
      (node (ref "IC1") (pin "1") (pinfunction "CS#_1") (pintype "passive"))
      (node (ref "R34") (pin "2") (pinfunction "2_2") (pintype "passive"))
      (node (ref "U1") (pin "36") (pinfunction "IOT_48B_36") (pintype "bidirectional"))
    )
    (net (code "70") (name "/{slash}CS_uC") (class "Default")
      (node (ref "U1") (pin "48") (pinfunction "IOB_4A_48") (pintype "bidirectional"))
      (node (ref "U2") (pin "44") (pinfunction "PB4_[~{SS}/OC0B/PCINT12]_44") (pintype "bidirectional"))
    )
    (net (code "71") (name "DGND") (class "Default")
      (node (ref "C4") (pin "1") (pinfunction "1_1") (pintype "passive"))
      (node (ref "IC1") (pin "4") (pinfunction "VSS_4") (pintype "passive"))
      (node (ref "IC2") (pin "4") (pinfunction "GND_4") (pintype "passive"))
      (node (ref "IC3") (pin "4") (pinfunction "GND_4") (pintype "passive"))
      (node (ref "P5") (pin "10") (pinfunction "GND_10") (pintype "passive"))
      (node (ref "P5") (pin "5") (pinfunction "GND_5") (pintype "passive"))
      (node (ref "P5") (pin "6") (pinfunction "GND_6") (pintype "passive"))
      (node (ref "P5") (pin "7") (pinfunction "GND_7") (pintype "passive"))
      (node (ref "P5") (pin "8") (pinfunction "GND_8") (pintype "passive"))
      (node (ref "P7") (pin "3") (pinfunction "3_3") (pintype "passive"))
      (node (ref "R28") (pin "1") (pinfunction "1_1") (pintype "passive"))
      (node (ref "R29") (pin "1") (pinfunction "1_1") (pintype "passive"))
      (node (ref "S1") (pin "2") (pinfunction "2_2") (pintype "passive"))
      (node (ref "S2") (pin "2") (pinfunction "2_2") (pintype "passive"))
      (node (ref "S3") (pin "2") (pinfunction "2_2") (pintype "passive"))
      (node (ref "S4") (pin "2") (pinfunction "2_2") (pintype "passive"))
      (node (ref "S5") (pin "2") (pinfunction "2_2") (pintype "passive"))
      (node (ref "S6") (pin "2") (pinfunction "2_2") (pintype "passive"))
      (node (ref "U1") (pin "EP") (pinfunction "GND_EP") (pintype "power_in"))
      (node (ref "U2") (pin "18") (pinfunction "GND_18") (pintype "power_in"))
      (node (ref "U2") (pin "28") (pinfunction "GND_28") (pintype "power_in"))
      (node (ref "U2") (pin "39") (pinfunction "GND_39") (pintype "power_in"))
      (node (ref "U2") (pin "6") (pinfunction "GND_6") (pintype "power_in"))
      (node (ref "U4") (pin "2") (pinfunction "GND_2") (pintype "power_in"))
      (node (ref "U6") (pin "1") (pinfunction "1_1") (pintype "passive"))
    )
    (net (code "72") (name "Net-(D1-K)") (class "Default")
      (node (ref "D1") (pin "2") (pinfunction "K_2") (pintype "passive"))
      (node (ref "R1") (pin "2") (pinfunction "2_2") (pintype "passive"))
    )
    (net (code "73") (name "Net-(D2-K)") (class "Default")
      (node (ref "D2") (pin "2") (pinfunction "K_2") (pintype "passive"))
      (node (ref "R2") (pin "2") (pinfunction "2_2") (pintype "passive"))
    )
    (net (code "74") (name "Net-(D5-K)") (class "Default")
      (node (ref "D5") (pin "2") (pinfunction "K_2") (pintype "passive"))
      (node (ref "R28") (pin "2") (pinfunction "2_2") (pintype "passive"))
    )
    (net (code "75") (name "Net-(D6-K)") (class "Default")
      (node (ref "D6") (pin "2") (pinfunction "K_2") (pintype "passive"))
      (node (ref "R29") (pin "2") (pinfunction "2_2") (pintype "passive"))
    )
    (net (code "76") (name "Net-(D9-K)") (class "Default")
      (node (ref "D9") (pin "2") (pinfunction "K_2") (pintype "passive"))
      (node (ref "R42") (pin "2") (pinfunction "2_2") (pintype "passive"))
    )
    (net (code "77") (name "Net-(IC3-~{CS})") (class "Default")
      (node (ref "IC3") (pin "1") (pinfunction "~{CS}_1") (pintype "passive"))
      (node (ref "P6") (pin "2") (pinfunction "2_2") (pintype "passive"))
      (node (ref "R45") (pin "2") (pinfunction "2_2") (pintype "passive"))
    )
    (net (code "78") (name "VCC_5V") (class "Default")
      (node (ref "P5") (pin "9") (pinfunction "OUT_5V_9") (pintype "passive"))
      (node (ref "R43") (pin "1") (pinfunction "1_1") (pintype "passive"))
      (node (ref "R44") (pin "1") (pinfunction "1_1") (pintype "passive"))
    )
    (net (code "79") (name "VDD_1.2V") (class "Default")
      (node (ref "U1") (pin "29") (pinfunction "VCCPLL_29") (pintype "power_in"))
      (node (ref "U1") (pin "30") (pinfunction "VCC_30") (pintype "power_in"))
      (node (ref "U1") (pin "5") (pinfunction "VCC_5") (pintype "power_in"))
    )
    (net (code "80") (name "VDD_3.3V") (class "Default")
      (node (ref "C4") (pin "2") (pinfunction "2_2") (pintype "passive"))
      (node (ref "D1") (pin "1") (pinfunction "A_1") (pintype "passive"))
      (node (ref "D2") (pin "1") (pinfunction "A_1") (pintype "passive"))
      (node (ref "D9") (pin "1") (pinfunction "A_1") (pintype "passive"))
      (node (ref "IC1") (pin "8") (pinfunction "VDD_8") (pintype "passive"))
      (node (ref "IC2") (pin "8") (pinfunction "VCC_8") (pintype "passive"))
      (node (ref "IC3") (pin "8") (pinfunction "VCC_8") (pintype "passive"))
      (node (ref "P7") (pin "4") (pinfunction "4_4") (pintype "passive"))
      (node (ref "Q1") (pin "1") (pinfunction "G_1") (pintype "passive"))
      (node (ref "Q2") (pin "1") (pinfunction "G_1") (pintype "passive"))
      (node (ref "R11") (pin "1") (pinfunction "1_1") (pintype "passive"))
      (node (ref "R12") (pin "1") (pinfunction "1_1") (pintype "passive"))
      (node (ref "R13") (pin "1") (pinfunction "1_1") (pintype "passive"))
      (node (ref "R14") (pin "1") (pinfunction "1_1") (pintype "passive"))
      (node (ref "R15") (pin "1") (pinfunction "1_1") (pintype "passive"))
      (node (ref "R16") (pin "1") (pinfunction "1_1") (pintype "passive"))
      (node (ref "R17") (pin "1") (pinfunction "1_1") (pintype "passive"))
      (node (ref "R26") (pin "1") (pinfunction "1_1") (pintype "passive"))
      (node (ref "R32") (pin "1") (pinfunction "1_1") (pintype "passive"))
      (node (ref "R33") (pin "1") (pinfunction "1_1") (pintype "passive"))
      (node (ref "R34") (pin "1") (pinfunction "1_1") (pintype "passive"))
      (node (ref "R41") (pin "1") (pinfunction "1_1") (pintype "passive"))
      (node (ref "R45") (pin "1") (pinfunction "1_1") (pintype "passive"))
      (node (ref "R46") (pin "1") (pinfunction "1_1") (pintype "passive"))
      (node (ref "R47") (pin "1") (pinfunction "1_1") (pintype "passive"))
      (node (ref "U1") (pin "1") (pinfunction "VCCIO_2_1") (pintype "power_in"))
      (node (ref "U1") (pin "22") (pinfunction "SPI_VCCIO_1_22") (pintype "power_in"))
      (node (ref "U1") (pin "24") (pinfunction "VPP_2V5_24") (pintype "power_in"))
      (node (ref "U1") (pin "33") (pinfunction "VCCIO_0_33") (pintype "power_in"))
      (node (ref "U2") (pin "17") (pinfunction "VCC_17") (pintype "power_in"))
      (node (ref "U2") (pin "27") (pinfunction "AVCC_27") (pintype "power_in"))
      (node (ref "U2") (pin "29") (pinfunction "AREF_29") (pintype "power_in"))
      (node (ref "U2") (pin "38") (pinfunction "VCC_38") (pintype "power_in"))
      (node (ref "U2") (pin "5") (pinfunction "VCC_5") (pintype "power_in"))
      (node (ref "U4") (pin "1") (pinfunction "en_1") (pintype "input"))
      (node (ref "U4") (pin "4") (pinfunction "VCCO_4") (pintype "power_in"))
    )
    (net (code "81") (name "unconnected-(P5-NC-Pad4)") (class "Default")
      (node (ref "P5") (pin "4") (pinfunction "NC_4") (pintype "passive+no_connect"))
    )
    (net (code "82") (name "unconnected-(P5-NC-Pad11)") (class "Default")
      (node (ref "P5") (pin "11") (pinfunction "NC_11") (pintype "passive+no_connect"))
    )
    (net (code "83") (name "unconnected-(P5-NC-Pad12)") (class "Default")
      (node (ref "P5") (pin "12") (pinfunction "NC_12") (pintype "passive+no_connect"))
    )
    (net (code "84") (name "unconnected-(P5-NC-Pad15)") (class "Default")
      (node (ref "P5") (pin "15") (pinfunction "NC_15") (pintype "passive+no_connect"))
    )
    (net (code "85") (name "unconnected-(U2-PA5_[ADC5{slash}PCINT5]-Pad32)") (class "Default")
      (node (ref "U2") (pin "32") (pinfunction "PA5_[ADC5/PCINT5]_32") (pintype "bidirectional"))
    )
    (net (code "86") (name "unconnected-(U2-PA6_[ADC6{slash}PCINT6]-Pad31)") (class "Default")
      (node (ref "U2") (pin "31") (pinfunction "PA6_[ADC6/PCINT6]_31") (pintype "bidirectional"))
    )
    (net (code "87") (name "unconnected-(U2-PA7_[ADC7{slash}PCINT7]-Pad30)") (class "Default")
      (node (ref "U2") (pin "30") (pinfunction "PA7_[ADC7/PCINT7]_30") (pintype "bidirectional"))
    )
    (net (code "88") (name "unconnected-(U2-PB2_[AIN0{slash}INT2{slash}PCINT10]-Pad42)") (class "Default")
      (node (ref "U2") (pin "42") (pinfunction "PB2_[AIN0/INT2/PCINT10]_42") (pintype "bidirectional"))
    )
    (net (code "89") (name "unconnected-(U2-PB3_[AIN1{slash}OC0A{slash}PCINT11]-Pad43)") (class "Default")
      (node (ref "U2") (pin "43") (pinfunction "PB3_[AIN1/OC0A/PCINT11]_43") (pintype "bidirectional"))
    )
    (net (code "90") (name "unconnected-(U2-PC6_[TOSC1{slash}PCINT22]-Pad25)") (class "Default")
      (node (ref "U2") (pin "25") (pinfunction "PC6_[TOSC1/PCINT22]_25") (pintype "bidirectional"))
    )
    (net (code "91") (name "unconnected-(U2-XTAL2-Pad7)") (class "Default")
      (node (ref "U2") (pin "7") (pinfunction "XTAL2_7") (pintype "passive+no_connect"))
    )
    (net (code "92") (name "unconnected-(U6-Pad2)") (class "Default")
      (node (ref "U6") (pin "2") (pinfunction "2_2") (pintype "passive+no_connect"))
    )
    (net (code "93") (name "unconnected-(U6-Pad4)") (class "Default")
      (node (ref "U6") (pin "4") (pinfunction "4_4") (pintype "passive+no_connect"))
    )
  )
)
